# Electrode_Array_Hex.net
KiCad netlist of a schematic drawn in Altium Designer
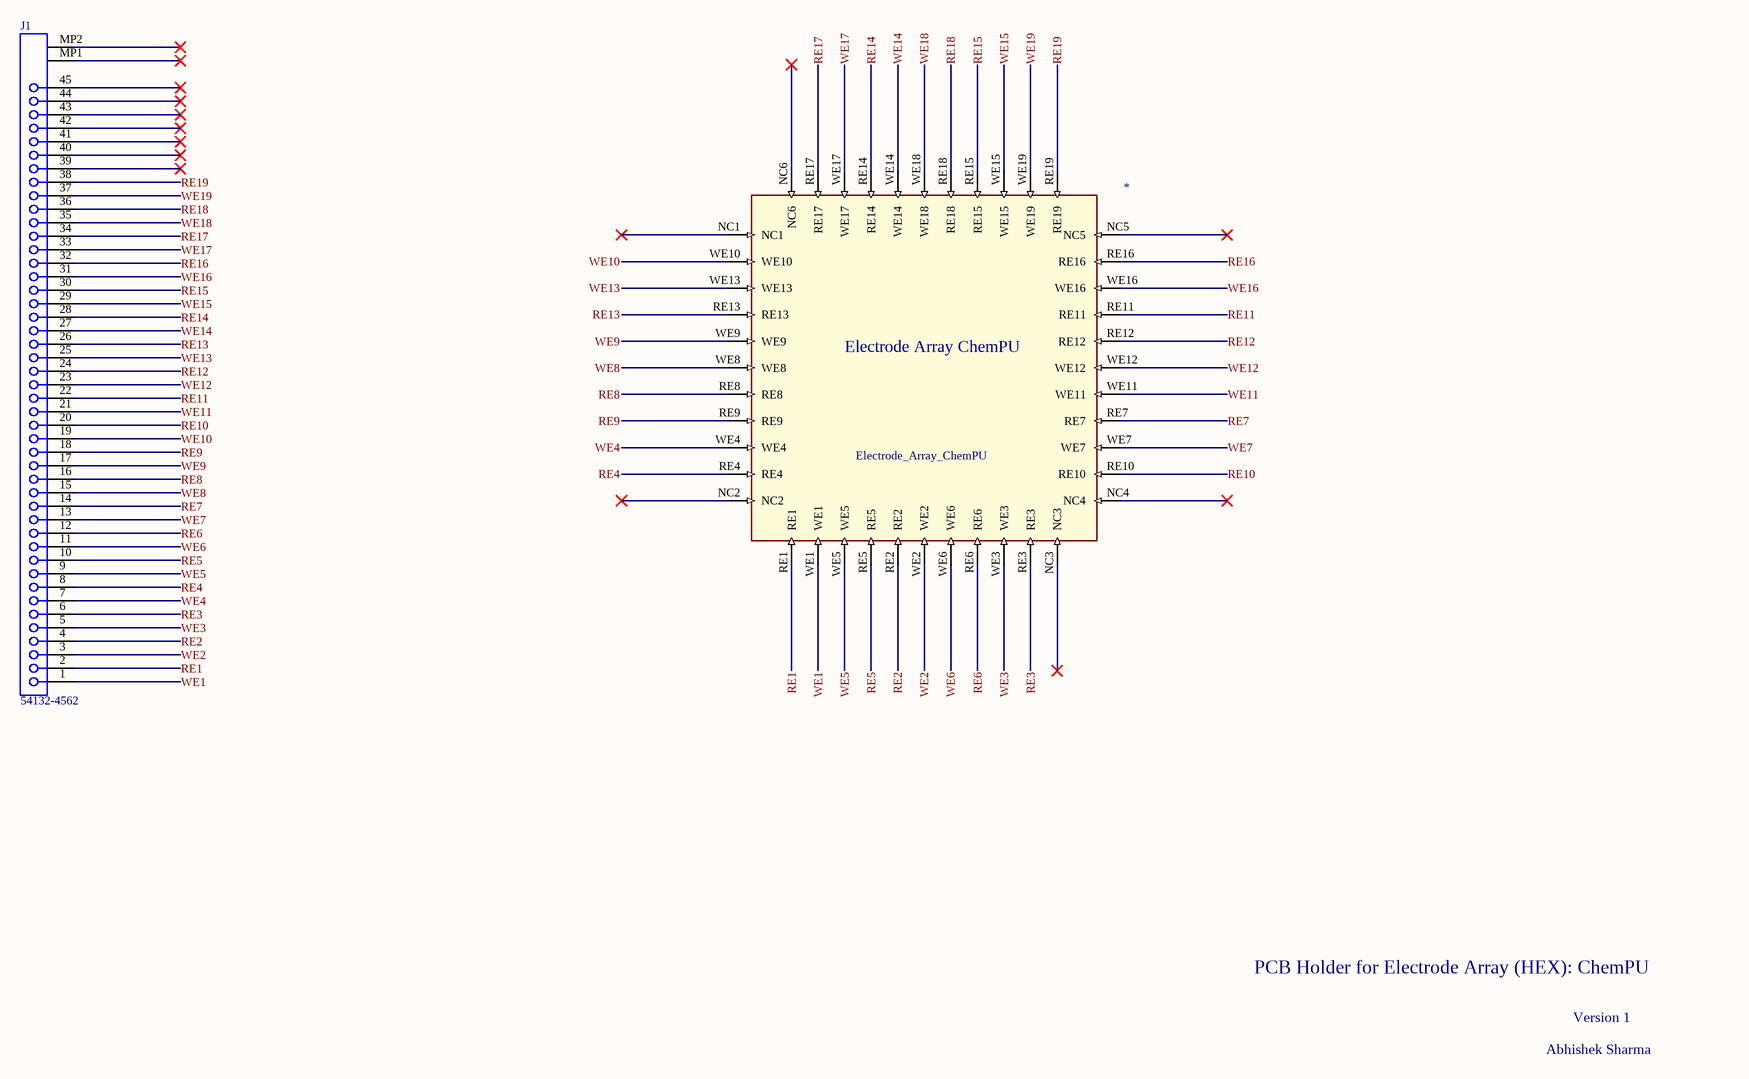
[diagram p0: Electrode_Array_Hex.SchDoc]

(export (version "E")
  (design (tool "Eeschema 10.0.6"))
  (components
    (comp (ref "*")
      (value "Electrode_Array_ChemPU")
      (footprint "PCBComponent_1")
      (libsource (lib "Electrode_Array_Hex") (part "Component_1"))
    )
    (comp (ref "J1")
      (value "54132-4562")
      (footprint "MOLX-54132-4562")
      (fields (field (name "MANUFACTURER") "Molex"))
      (libsource (lib "Altium Content Vault") (part "MOLX-54132-4562"))
    )
  )
  (nets
    (net (code "1") (name "/RE1") (class "Default")
      (node (ref "*") (pin "RE1") (pinfunction "RE1_RE1") (pintype "input"))
      (node (ref "J1") (pin "2") (pinfunction "2_2") (pintype "passive"))
    )
    (net (code "2") (name "/RE2") (class "Default")
      (node (ref "*") (pin "RE2") (pinfunction "RE2_RE2") (pintype "input"))
      (node (ref "J1") (pin "4") (pinfunction "4_4") (pintype "passive"))
    )
    (net (code "3") (name "/RE3") (class "Default")
      (node (ref "*") (pin "RE3") (pinfunction "RE3_RE3") (pintype "input"))
      (node (ref "J1") (pin "6") (pinfunction "6_6") (pintype "passive"))
    )
    (net (code "4") (name "/RE4") (class "Default")
      (node (ref "*") (pin "RE4") (pinfunction "RE4_RE4") (pintype "input"))
      (node (ref "J1") (pin "8") (pinfunction "8_8") (pintype "passive"))
    )
    (net (code "5") (name "/RE5") (class "Default")
      (node (ref "*") (pin "RE5") (pinfunction "RE5_RE5") (pintype "input"))
      (node (ref "J1") (pin "10") (pinfunction "10_10") (pintype "passive"))
    )
    (net (code "6") (name "/RE6") (class "Default")
      (node (ref "*") (pin "RE6") (pinfunction "RE6_RE6") (pintype "input"))
      (node (ref "J1") (pin "12") (pinfunction "12_12") (pintype "passive"))
    )
    (net (code "7") (name "/RE7") (class "Default")
      (node (ref "*") (pin "RE7") (pinfunction "RE7_RE7") (pintype "input"))
      (node (ref "J1") (pin "14") (pinfunction "14_14") (pintype "passive"))
    )
    (net (code "8") (name "/RE8") (class "Default")
      (node (ref "*") (pin "RE8") (pinfunction "RE8_RE8") (pintype "input"))
      (node (ref "J1") (pin "16") (pinfunction "16_16") (pintype "passive"))
    )
    (net (code "9") (name "/RE9") (class "Default")
      (node (ref "*") (pin "RE9") (pinfunction "RE9_RE9") (pintype "input"))
      (node (ref "J1") (pin "18") (pinfunction "18_18") (pintype "passive"))
    )
    (net (code "10") (name "/RE10") (class "Default")
      (node (ref "*") (pin "RE10") (pinfunction "RE10_RE10") (pintype "input"))
      (node (ref "J1") (pin "20") (pinfunction "20_20") (pintype "passive"))
    )
    (net (code "11") (name "/RE11") (class "Default")
      (node (ref "*") (pin "RE11") (pinfunction "RE11_RE11") (pintype "input"))
      (node (ref "J1") (pin "22") (pinfunction "22_22") (pintype "passive"))
    )
    (net (code "12") (name "/RE12") (class "Default")
      (node (ref "*") (pin "RE12") (pinfunction "RE12_RE12") (pintype "input"))
      (node (ref "J1") (pin "24") (pinfunction "24_24") (pintype "passive"))
    )
    (net (code "13") (name "/RE13") (class "Default")
      (node (ref "*") (pin "RE13") (pinfunction "RE13_RE13") (pintype "input"))
      (node (ref "J1") (pin "26") (pinfunction "26_26") (pintype "passive"))
    )
    (net (code "14") (name "/RE14") (class "Default")
      (node (ref "*") (pin "RE14") (pinfunction "RE14_RE14") (pintype "input"))
      (node (ref "J1") (pin "28") (pinfunction "28_28") (pintype "passive"))
    )
    (net (code "15") (name "/RE15") (class "Default")
      (node (ref "*") (pin "RE15") (pinfunction "RE15_RE15") (pintype "input"))
      (node (ref "J1") (pin "30") (pinfunction "30_30") (pintype "passive"))
    )
    (net (code "16") (name "/RE16") (class "Default")
      (node (ref "*") (pin "RE16") (pinfunction "RE16_RE16") (pintype "input"))
      (node (ref "J1") (pin "32") (pinfunction "32_32") (pintype "passive"))
    )
    (net (code "17") (name "/RE17") (class "Default")
      (node (ref "*") (pin "RE17") (pinfunction "RE17_RE17") (pintype "input"))
      (node (ref "J1") (pin "34") (pinfunction "34_34") (pintype "passive"))
    )
    (net (code "18") (name "/RE18") (class "Default")
      (node (ref "*") (pin "RE18") (pinfunction "RE18_RE18") (pintype "input"))
      (node (ref "J1") (pin "36") (pinfunction "36_36") (pintype "passive"))
    )
    (net (code "19") (name "/RE19") (class "Default")
      (node (ref "*") (pin "RE19") (pinfunction "RE19_RE19") (pintype "input"))
      (node (ref "J1") (pin "38") (pinfunction "38_38") (pintype "passive"))
    )
    (net (code "20") (name "/WE1") (class "Default")
      (node (ref "*") (pin "WE1") (pinfunction "WE1_WE1") (pintype "input"))
      (node (ref "J1") (pin "1") (pinfunction "1_1") (pintype "passive"))
    )
    (net (code "21") (name "/WE2") (class "Default")
      (node (ref "*") (pin "WE2") (pinfunction "WE2_WE2") (pintype "input"))
      (node (ref "J1") (pin "3") (pinfunction "3_3") (pintype "passive"))
    )
    (net (code "22") (name "/WE3") (class "Default")
      (node (ref "*") (pin "WE3") (pinfunction "WE3_WE3") (pintype "input"))
      (node (ref "J1") (pin "5") (pinfunction "5_5") (pintype "passive"))
    )
    (net (code "23") (name "/WE4") (class "Default")
      (node (ref "*") (pin "WE4") (pinfunction "WE4_WE4") (pintype "input"))
      (node (ref "J1") (pin "7") (pinfunction "7_7") (pintype "passive"))
    )
    (net (code "24") (name "/WE5") (class "Default")
      (node (ref "*") (pin "WE5") (pinfunction "WE5_WE5") (pintype "input"))
      (node (ref "J1") (pin "9") (pinfunction "9_9") (pintype "passive"))
    )
    (net (code "25") (name "/WE6") (class "Default")
      (node (ref "*") (pin "WE6") (pinfunction "WE6_WE6") (pintype "input"))
      (node (ref "J1") (pin "11") (pinfunction "11_11") (pintype "passive"))
    )
    (net (code "26") (name "/WE7") (class "Default")
      (node (ref "*") (pin "WE7") (pinfunction "WE7_WE7") (pintype "input"))
      (node (ref "J1") (pin "13") (pinfunction "13_13") (pintype "passive"))
    )
    (net (code "27") (name "/WE8") (class "Default")
      (node (ref "*") (pin "WE8") (pinfunction "WE8_WE8") (pintype "input"))
      (node (ref "J1") (pin "15") (pinfunction "15_15") (pintype "passive"))
    )
    (net (code "28") (name "/WE9") (class "Default")
      (node (ref "*") (pin "WE9") (pinfunction "WE9_WE9") (pintype "input"))
      (node (ref "J1") (pin "17") (pinfunction "17_17") (pintype "passive"))
    )
    (net (code "29") (name "/WE10") (class "Default")
      (node (ref "*") (pin "WE10") (pinfunction "WE10_WE10") (pintype "input"))
      (node (ref "J1") (pin "19") (pinfunction "19_19") (pintype "passive"))
    )
    (net (code "30") (name "/WE11") (class "Default")
      (node (ref "*") (pin "WE11") (pinfunction "WE11_WE11") (pintype "input"))
      (node (ref "J1") (pin "21") (pinfunction "21_21") (pintype "passive"))
    )
    (net (code "31") (name "/WE12") (class "Default")
      (node (ref "*") (pin "WE12") (pinfunction "WE12_WE12") (pintype "input"))
      (node (ref "J1") (pin "23") (pinfunction "23_23") (pintype "passive"))
    )
    (net (code "32") (name "/WE13") (class "Default")
      (node (ref "*") (pin "WE13") (pinfunction "WE13_WE13") (pintype "input"))
      (node (ref "J1") (pin "25") (pinfunction "25_25") (pintype "passive"))
    )
    (net (code "33") (name "/WE14") (class "Default")
      (node (ref "*") (pin "WE14") (pinfunction "WE14_WE14") (pintype "input"))
      (node (ref "J1") (pin "27") (pinfunction "27_27") (pintype "passive"))
    )
    (net (code "34") (name "/WE15") (class "Default")
      (node (ref "*") (pin "WE15") (pinfunction "WE15_WE15") (pintype "input"))
      (node (ref "J1") (pin "29") (pinfunction "29_29") (pintype "passive"))
    )
    (net (code "35") (name "/WE16") (class "Default")
      (node (ref "*") (pin "WE16") (pinfunction "WE16_WE16") (pintype "input"))
      (node (ref "J1") (pin "31") (pinfunction "31_31") (pintype "passive"))
    )
    (net (code "36") (name "/WE17") (class "Default")
      (node (ref "*") (pin "WE17") (pinfunction "WE17_WE17") (pintype "input"))
      (node (ref "J1") (pin "33") (pinfunction "33_33") (pintype "passive"))
    )
    (net (code "37") (name "/WE18") (class "Default")
      (node (ref "*") (pin "WE18") (pinfunction "WE18_WE18") (pintype "input"))
      (node (ref "J1") (pin "35") (pinfunction "35_35") (pintype "passive"))
    )
    (net (code "38") (name "/WE19") (class "Default")
      (node (ref "*") (pin "WE19") (pinfunction "WE19_WE19") (pintype "input"))
      (node (ref "J1") (pin "37") (pinfunction "37_37") (pintype "passive"))
    )
    (net (code "39") (name "unconnected-(*-PadNC1)") (class "Default")
      (node (ref "*") (pin "NC1") (pinfunction "NC1_NC1") (pintype "input+no_connect"))
    )
    (net (code "40") (name "unconnected-(*-PadNC2)") (class "Default")
      (node (ref "*") (pin "NC2") (pinfunction "NC2_NC2") (pintype "input+no_connect"))
    )
    (net (code "41") (name "unconnected-(*-PadNC3)") (class "Default")
      (node (ref "*") (pin "NC3") (pinfunction "NC3_NC3") (pintype "input+no_connect"))
    )
    (net (code "42") (name "unconnected-(*-PadNC4)") (class "Default")
      (node (ref "*") (pin "NC4") (pinfunction "NC4_NC4") (pintype "input+no_connect"))
    )
    (net (code "43") (name "unconnected-(*-PadNC5)") (class "Default")
      (node (ref "*") (pin "NC5") (pinfunction "NC5_NC5") (pintype "input+no_connect"))
    )
    (net (code "44") (name "unconnected-(*-PadNC6)") (class "Default")
      (node (ref "*") (pin "NC6") (pinfunction "NC6_NC6") (pintype "input+no_connect"))
    )
    (net (code "45") (name "unconnected-(J1-Pad39)") (class "Default")
      (node (ref "J1") (pin "39") (pinfunction "39_39") (pintype "passive+no_connect"))
    )
    (net (code "46") (name "unconnected-(J1-Pad40)") (class "Default")
      (node (ref "J1") (pin "40") (pinfunction "40_40") (pintype "passive+no_connect"))
    )
    (net (code "47") (name "unconnected-(J1-Pad41)") (class "Default")
      (node (ref "J1") (pin "41") (pinfunction "41_41") (pintype "passive+no_connect"))
    )
    (net (code "48") (name "unconnected-(J1-Pad42)") (class "Default")
      (node (ref "J1") (pin "42") (pinfunction "42_42") (pintype "passive+no_connect"))
    )
    (net (code "49") (name "unconnected-(J1-Pad43)") (class "Default")
      (node (ref "J1") (pin "43") (pinfunction "43_43") (pintype "passive+no_connect"))
    )
    (net (code "50") (name "unconnected-(J1-Pad44)") (class "Default")
      (node (ref "J1") (pin "44") (pinfunction "44_44") (pintype "passive+no_connect"))
    )
    (net (code "51") (name "unconnected-(J1-Pad45)") (class "Default")
      (node (ref "J1") (pin "45") (pinfunction "45_45") (pintype "passive+no_connect"))
    )
    (net (code "52") (name "unconnected-(J1-PadMP1)") (class "Default")
      (node (ref "J1") (pin "MP1") (pinfunction "MP1_MP1") (pintype "passive+no_connect"))
    )
    (net (code "53") (name "unconnected-(J1-PadMP2)") (class "Default")
      (node (ref "J1") (pin "MP2") (pinfunction "MP2_MP2") (pintype "passive+no_connect"))
    )
  )
)
